# RADC-ModuleConnect-S06-V00.net
KiCad netlist of a schematic drawn in Altium Designer
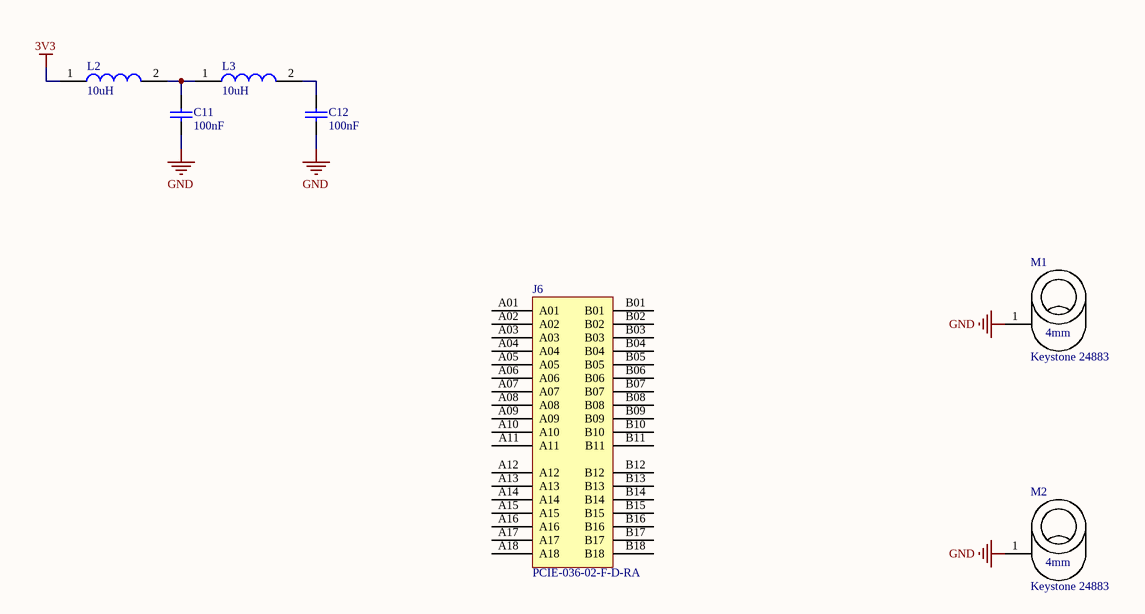
[diagram p0: RADC-ModuleConnect-S06-V00.SchDoc]

(export (version "E")
  (design (tool "Eeschema 10.0.6"))
  (components
    (comp (ref "C11")
      (value "100nF")
      (footprint "Cap_Ceramic_0603")
      (description "Capacitor, Ceramic, SMD, 100nF, 50V, 5%, X7R, 0603")
      (libsource (lib "StandardCapacitors") (part "100nF 50V 5% X7R 0603"))
    )
    (comp (ref "C12")
      (value "100nF")
      (footprint "Cap_Ceramic_0603")
      (description "Capacitor, Ceramic, SMD, 100nF, 50V, 5%, X7R, 0603")
      (libsource (lib "StandardCapacitors") (part "100nF 50V 5% X7R 0603"))
    )
    (comp (ref "J6")
      (value "PCIE-036-02-F-D-RA")
      (footprint "PCIE-036-02-F-D-RA")
      (description "36 Position Female Connector PCI Express™ Gold 0.039\" (1.00mm) Black")
      (libsource (lib "QUTMS_PCIConnectorLibrary") (part "PCIE-036-02-F-D-RA"))
    )
    (comp (ref "L2")
      (value "10uH")
      (footprint "Inductor_0603")
      (description "10uH, 10%, 0603")
      (libsource (lib "QUTMS_InductorLibrary") (part "10uH, 10%, 0603"))
    )
    (comp (ref "L3")
      (value "10uH")
      (footprint "Inductor_0603")
      (description "10uH, 10%, 0603")
      (libsource (lib "QUTMS_InductorLibrary") (part "10uH, 10%, 0603"))
    )
    (comp (ref "M1")
      (value "Keystone 24883")
      (footprint "Keystone 24883")
      (description "Round Standoff Threaded M3x0.5 Steel 0.160\" (4.06mm)")
      (libsource (lib "QUTMS_PCBLibrary") (part "Keystone 24883"))
    )
    (comp (ref "M2")
      (value "Keystone 24883")
      (footprint "Keystone 24883")
      (description "Round Standoff Threaded M3x0.5 Steel 0.160\" (4.06mm)")
      (libsource (lib "QUTMS_PCBLibrary") (part "Keystone 24883"))
    )
  )
  (nets
    (net (code "1") (name "3V3") (class "Default")
      (node (ref "L2") (pin "1") (pinfunction "1_1") (pintype "passive"))
    )
    (net (code "2") (name "GND") (class "Default")
      (node (ref "C11") (pin "1") (pinfunction "1_1") (pintype "passive"))
      (node (ref "C12") (pin "1") (pinfunction "1_1") (pintype "passive"))
      (node (ref "M1") (pin "1") (pinfunction "1_1") (pintype "passive"))
      (node (ref "M2") (pin "1") (pinfunction "1_1") (pintype "passive"))
    )
    (net (code "3") (name "Net-(C11-Pad2)") (class "Default")
      (node (ref "C11") (pin "2") (pinfunction "2_2") (pintype "passive"))
      (node (ref "L2") (pin "2") (pinfunction "2_2") (pintype "passive"))
      (node (ref "L3") (pin "1") (pinfunction "1_1") (pintype "passive"))
    )
    (net (code "4") (name "Net-(C12-Pad2)") (class "Default")
      (node (ref "C12") (pin "2") (pinfunction "2_2") (pintype "passive"))
      (node (ref "L3") (pin "2") (pinfunction "2_2") (pintype "passive"))
    )
    (net (code "5") (name "unconnected-(J6-PadA01)") (class "Default")
      (node (ref "J6") (pin "A01") (pinfunction "A01_A01") (pintype "passive"))
    )
    (net (code "6") (name "unconnected-(J6-PadA02)") (class "Default")
      (node (ref "J6") (pin "A02") (pinfunction "A02_A02") (pintype "passive"))
    )
    (net (code "7") (name "unconnected-(J6-PadA03)") (class "Default")
      (node (ref "J6") (pin "A03") (pinfunction "A03_A03") (pintype "passive"))
    )
    (net (code "8") (name "unconnected-(J6-PadA04)") (class "Default")
      (node (ref "J6") (pin "A04") (pinfunction "A04_A04") (pintype "passive"))
    )
    (net (code "9") (name "unconnected-(J6-PadA05)") (class "Default")
      (node (ref "J6") (pin "A05") (pinfunction "A05_A05") (pintype "passive"))
    )
    (net (code "10") (name "unconnected-(J6-PadA06)") (class "Default")
      (node (ref "J6") (pin "A06") (pinfunction "A06_A06") (pintype "passive"))
    )
    (net (code "11") (name "unconnected-(J6-PadA07)") (class "Default")
      (node (ref "J6") (pin "A07") (pinfunction "A07_A07") (pintype "passive"))
    )
    (net (code "12") (name "unconnected-(J6-PadA08)") (class "Default")
      (node (ref "J6") (pin "A08") (pinfunction "A08_A08") (pintype "passive"))
    )
    (net (code "13") (name "unconnected-(J6-PadA09)") (class "Default")
      (node (ref "J6") (pin "A09") (pinfunction "A09_A09") (pintype "passive"))
    )
    (net (code "14") (name "unconnected-(J6-PadA10)") (class "Default")
      (node (ref "J6") (pin "A10") (pinfunction "A10_A10") (pintype "passive"))
    )
    (net (code "15") (name "unconnected-(J6-PadA11)") (class "Default")
      (node (ref "J6") (pin "A11") (pinfunction "A11_A11") (pintype "passive"))
    )
    (net (code "16") (name "unconnected-(J6-PadA12)") (class "Default")
      (node (ref "J6") (pin "A12") (pinfunction "A12_A12") (pintype "passive"))
    )
    (net (code "17") (name "unconnected-(J6-PadA13)") (class "Default")
      (node (ref "J6") (pin "A13") (pinfunction "A13_A13") (pintype "passive"))
    )
    (net (code "18") (name "unconnected-(J6-PadA14)") (class "Default")
      (node (ref "J6") (pin "A14") (pinfunction "A14_A14") (pintype "passive"))
    )
    (net (code "19") (name "unconnected-(J6-PadA15)") (class "Default")
      (node (ref "J6") (pin "A15") (pinfunction "A15_A15") (pintype "passive"))
    )
    (net (code "20") (name "unconnected-(J6-PadA16)") (class "Default")
      (node (ref "J6") (pin "A16") (pinfunction "A16_A16") (pintype "passive"))
    )
    (net (code "21") (name "unconnected-(J6-PadA17)") (class "Default")
      (node (ref "J6") (pin "A17") (pinfunction "A17_A17") (pintype "passive"))
    )
    (net (code "22") (name "unconnected-(J6-PadA18)") (class "Default")
      (node (ref "J6") (pin "A18") (pinfunction "A18_A18") (pintype "passive"))
    )
    (net (code "23") (name "unconnected-(J6-PadB01)") (class "Default")
      (node (ref "J6") (pin "B01") (pinfunction "B01_B01") (pintype "passive"))
    )
    (net (code "24") (name "unconnected-(J6-PadB02)") (class "Default")
      (node (ref "J6") (pin "B02") (pinfunction "B02_B02") (pintype "passive"))
    )
    (net (code "25") (name "unconnected-(J6-PadB03)") (class "Default")
      (node (ref "J6") (pin "B03") (pinfunction "B03_B03") (pintype "passive"))
    )
    (net (code "26") (name "unconnected-(J6-PadB04)") (class "Default")
      (node (ref "J6") (pin "B04") (pinfunction "B04_B04") (pintype "passive"))
    )
    (net (code "27") (name "unconnected-(J6-PadB05)") (class "Default")
      (node (ref "J6") (pin "B05") (pinfunction "B05_B05") (pintype "passive"))
    )
    (net (code "28") (name "unconnected-(J6-PadB06)") (class "Default")
      (node (ref "J6") (pin "B06") (pinfunction "B06_B06") (pintype "passive"))
    )
    (net (code "29") (name "unconnected-(J6-PadB07)") (class "Default")
      (node (ref "J6") (pin "B07") (pinfunction "B07_B07") (pintype "passive"))
    )
    (net (code "30") (name "unconnected-(J6-PadB08)") (class "Default")
      (node (ref "J6") (pin "B08") (pinfunction "B08_B08") (pintype "passive"))
    )
    (net (code "31") (name "unconnected-(J6-PadB09)") (class "Default")
      (node (ref "J6") (pin "B09") (pinfunction "B09_B09") (pintype "passive"))
    )
    (net (code "32") (name "unconnected-(J6-PadB10)") (class "Default")
      (node (ref "J6") (pin "B10") (pinfunction "B10_B10") (pintype "passive"))
    )
    (net (code "33") (name "unconnected-(J6-PadB11)") (class "Default")
      (node (ref "J6") (pin "B11") (pinfunction "B11_B11") (pintype "passive"))
    )
    (net (code "34") (name "unconnected-(J6-PadB12)") (class "Default")
      (node (ref "J6") (pin "B12") (pinfunction "B12_B12") (pintype "passive"))
    )
    (net (code "35") (name "unconnected-(J6-PadB13)") (class "Default")
      (node (ref "J6") (pin "B13") (pinfunction "B13_B13") (pintype "passive"))
    )
    (net (code "36") (name "unconnected-(J6-PadB14)") (class "Default")
      (node (ref "J6") (pin "B14") (pinfunction "B14_B14") (pintype "passive"))
    )
    (net (code "37") (name "unconnected-(J6-PadB15)") (class "Default")
      (node (ref "J6") (pin "B15") (pinfunction "B15_B15") (pintype "passive"))
    )
    (net (code "38") (name "unconnected-(J6-PadB16)") (class "Default")
      (node (ref "J6") (pin "B16") (pinfunction "B16_B16") (pintype "passive"))
    )
    (net (code "39") (name "unconnected-(J6-PadB17)") (class "Default")
      (node (ref "J6") (pin "B17") (pinfunction "B17_B17") (pintype "passive"))
    )
    (net (code "40") (name "unconnected-(J6-PadB18)") (class "Default")
      (node (ref "J6") (pin "B18") (pinfunction "B18_B18") (pintype "passive"))
    )
  )
)
